# untitled.net
KiCad netlist of a schematic drawn in EAGLE
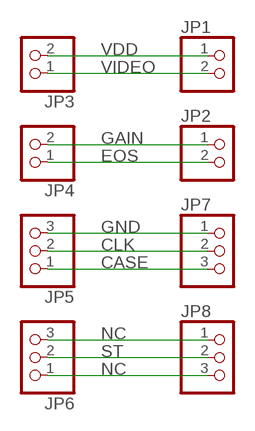
[diagram p0: schematic, sheet 1]

(export (version "E")
  (design (tool "Eeschema 10.0.6"))
  (components
    (comp (ref "JP1")
      (value "PINHD-1X2")
      (footprint "eagle-import:1X02")
      (libsource (lib "eagle-import") (part "PINHD-1X2"))
    )
    (comp (ref "JP2")
      (value "PINHD-1X2")
      (footprint "eagle-import:1X02")
      (libsource (lib "eagle-import") (part "PINHD-1X2"))
    )
    (comp (ref "JP3")
      (value "PINHD-1X2")
      (footprint "eagle-import:1X02")
      (libsource (lib "eagle-import") (part "PINHD-1X2"))
    )
    (comp (ref "JP4")
      (value "PINHD-1X2")
      (footprint "eagle-import:1X02")
      (libsource (lib "eagle-import") (part "PINHD-1X2"))
    )
    (comp (ref "JP5")
      (value "PINHD-1X3")
      (footprint "eagle-import:1X03")
      (libsource (lib "eagle-import") (part "PINHD-1X3"))
    )
    (comp (ref "JP6")
      (value "PINHD-1X3")
      (footprint "eagle-import:1X03")
      (libsource (lib "eagle-import") (part "PINHD-1X3"))
    )
    (comp (ref "JP7")
      (value "PINHD-1X3")
      (footprint "eagle-import:1X03")
      (libsource (lib "eagle-import") (part "PINHD-1X3"))
    )
    (comp (ref "JP8")
      (value "PINHD-1X3")
      (footprint "eagle-import:1X03")
      (libsource (lib "eagle-import") (part "PINHD-1X3"))
    )
  )
  (nets
    (net (code "1") (name "/CASE") (class "Default")
      (node (ref "JP5") (pin "1") (pinfunction "1_1") (pintype "passive"))
      (node (ref "JP7") (pin "3") (pinfunction "3_3") (pintype "passive"))
    )
    (net (code "2") (name "/CLK") (class "Default")
      (node (ref "JP5") (pin "2") (pinfunction "2_2") (pintype "passive"))
      (node (ref "JP7") (pin "2") (pinfunction "2_2") (pintype "passive"))
    )
    (net (code "3") (name "/EOS") (class "Default")
      (node (ref "JP2") (pin "2") (pinfunction "2_2") (pintype "passive"))
      (node (ref "JP4") (pin "1") (pinfunction "1_1") (pintype "passive"))
    )
    (net (code "4") (name "/GAIN") (class "Default")
      (node (ref "JP2") (pin "1") (pinfunction "1_1") (pintype "passive"))
      (node (ref "JP4") (pin "2") (pinfunction "2_2") (pintype "passive"))
    )
    (net (code "5") (name "/GND") (class "Default")
      (node (ref "JP5") (pin "3") (pinfunction "3_3") (pintype "passive"))
      (node (ref "JP7") (pin "1") (pinfunction "1_1") (pintype "passive"))
    )
    (net (code "6") (name "/NC") (class "Default")
      (node (ref "JP6") (pin "1") (pinfunction "1_1") (pintype "passive"))
      (node (ref "JP6") (pin "3") (pinfunction "3_3") (pintype "passive"))
      (node (ref "JP8") (pin "1") (pinfunction "1_1") (pintype "passive"))
      (node (ref "JP8") (pin "3") (pinfunction "3_3") (pintype "passive"))
    )
    (net (code "7") (name "/ST") (class "Default")
      (node (ref "JP6") (pin "2") (pinfunction "2_2") (pintype "passive"))
      (node (ref "JP8") (pin "2") (pinfunction "2_2") (pintype "passive"))
    )
    (net (code "8") (name "/VDD") (class "Default")
      (node (ref "JP1") (pin "1") (pinfunction "1_1") (pintype "passive"))
      (node (ref "JP3") (pin "2") (pinfunction "2_2") (pintype "passive"))
    )
    (net (code "9") (name "/VIDEO") (class "Default")
      (node (ref "JP1") (pin "2") (pinfunction "2_2") (pintype "passive"))
      (node (ref "JP3") (pin "1") (pinfunction "1_1") (pintype "passive"))
    )
  )
)
